# cameralight.net
KiCad netlist of a schematic drawn in EAGLE
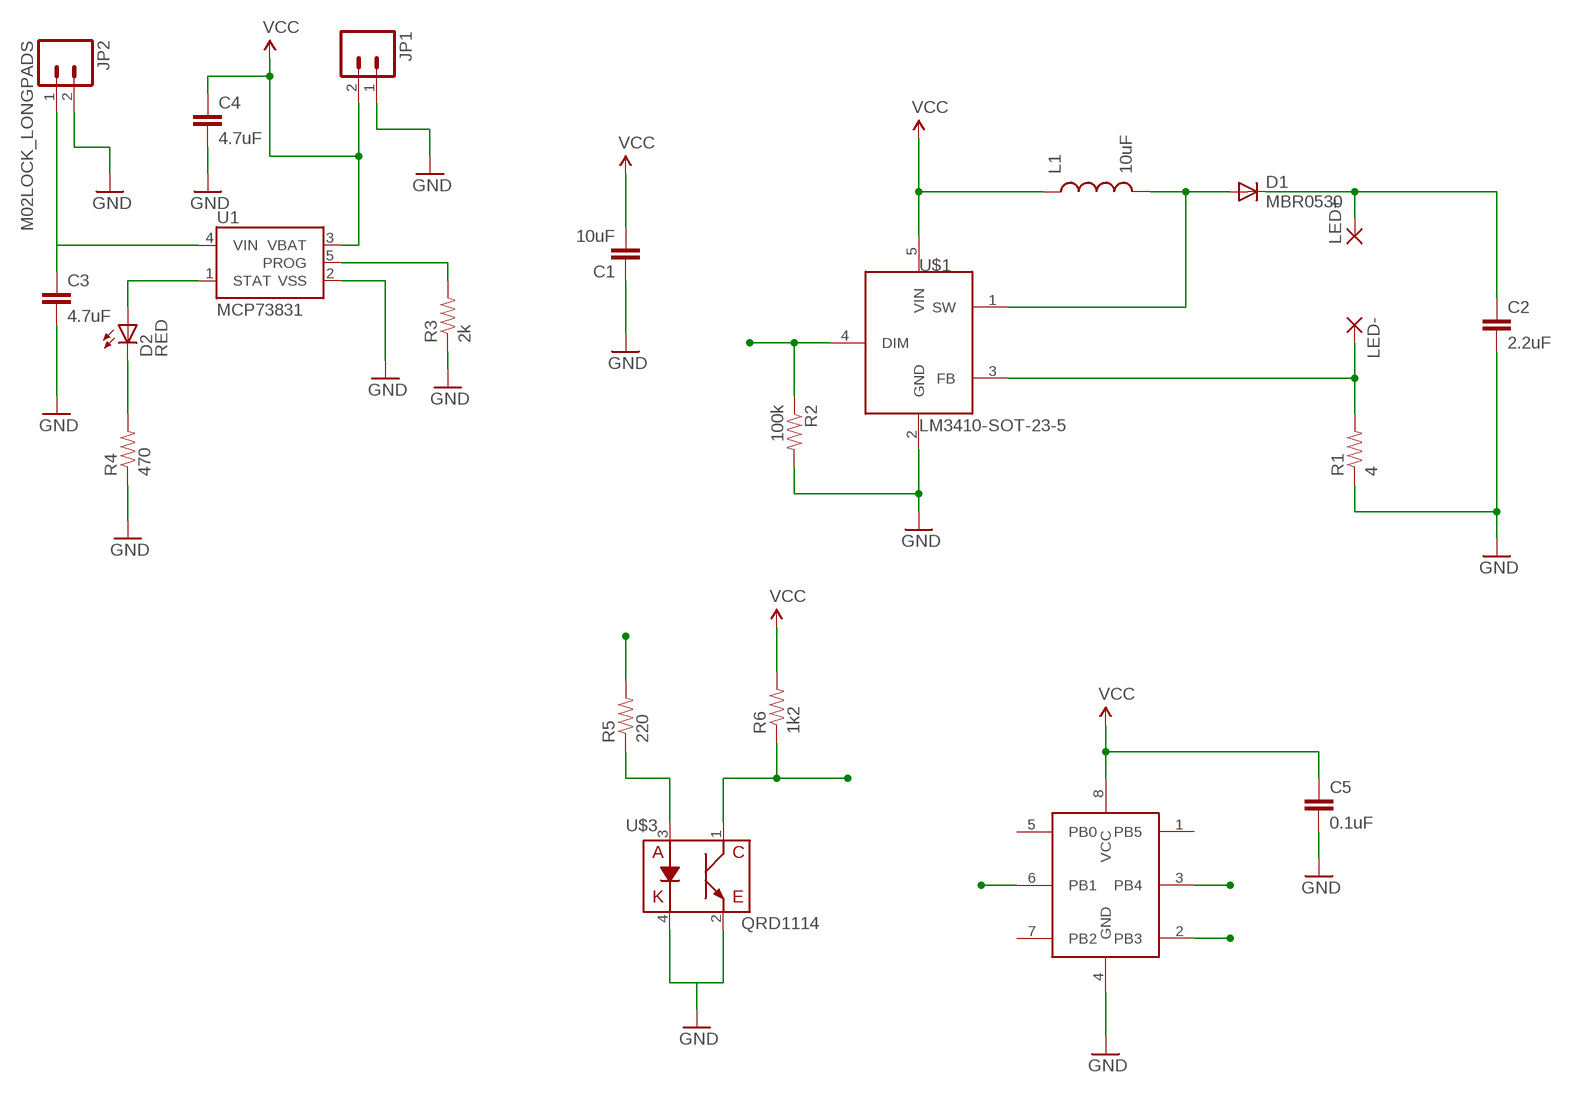
[diagram p0: schematic, sheet 1]

(export (version "E")
  (design (tool "Eeschema 10.0.6"))
  (components
    (comp (ref "C1")
      (value "10uF")
      (footprint "eagle-import:CTZ3")
      (libsource (lib "eagle-import") (part "SparkFun-Passives_CAPASMD"))
    )
    (comp (ref "C2")
      (value "2.2uF")
      (footprint "eagle-import:CTZ3")
      (libsource (lib "eagle-import") (part "SparkFun-Passives_CAPASMD"))
    )
    (comp (ref "C3")
      (value "4.7uF")
      (footprint "eagle-import:1206")
      (libsource (lib "eagle-import") (part "CAP1206"))
    )
    (comp (ref "C4")
      (value "4.7uF")
      (footprint "eagle-import:1206")
      (libsource (lib "eagle-import") (part "CAP1206"))
    )
    (comp (ref "C5")
      (value "0.1uF")
      (footprint "eagle-import:0603-CAP")
      (libsource (lib "eagle-import") (part "CAP0603-CAP"))
    )
    (comp (ref "D1")
      (value "MBR0530")
      (footprint "eagle-import:SOD123")
      (libsource (lib "eagle-import") (part "MBR0520LT"))
    )
    (comp (ref "D2")
      (value "RED")
      (footprint "eagle-import:LED-0603")
      (libsource (lib "eagle-import") (part "LED-RED0603"))
    )
    (comp (ref "JP1")
      (value "M02-JST-2MM-SMT")
      (footprint "eagle-import:JST-2-SMD")
      (libsource (lib "eagle-import") (part "M02-JST-2MM-SMT"))
    )
    (comp (ref "JP2")
      (value "M02LOCK_LONGPADS")
      (footprint "eagle-import:1X02_LOCK_LONGPADS")
      (libsource (lib "eagle-import") (part "M02LOCK_LONGPADS"))
    )
    (comp (ref "L1")
      (value "10uF")
      (footprint "eagle-import:CR54")
      (libsource (lib "eagle-import") (part "INDUCTORCR54"))
    )
    (comp (ref "LED+")
      (value "2,54/1,0")
      (footprint "eagle-import:2,54_1,0")
      (libsource (lib "eagle-import") (part "2,54/1,0"))
    )
    (comp (ref "LED-")
      (value "2,54/1,0")
      (footprint "eagle-import:2,54_1,0")
      (libsource (lib "eagle-import") (part "2,54/1,0"))
    )
    (comp (ref "R1")
      (value "4")
      (footprint "eagle-import:0603-RES")
      (libsource (lib "eagle-import") (part "RESISTOR0603-RES"))
    )
    (comp (ref "R2")
      (value "100k")
      (footprint "eagle-import:0603-RES")
      (libsource (lib "eagle-import") (part "RESISTOR0603-RES"))
    )
    (comp (ref "R3")
      (value "2k")
      (footprint "eagle-import:1206")
      (libsource (lib "eagle-import") (part "RESISTOR1206"))
    )
    (comp (ref "R4")
      (value "470")
      (footprint "eagle-import:0603-RES")
      (libsource (lib "eagle-import") (part "RESISTOR0603-RES"))
    )
    (comp (ref "R5")
      (value "220")
      (footprint "eagle-import:0603-RES")
      (libsource (lib "eagle-import") (part "RESISTOR0603-RES"))
    )
    (comp (ref "R6")
      (value "1k2")
      (footprint "eagle-import:0603-RES")
      (libsource (lib "eagle-import") (part "RESISTOR0603-RES"))
    )
    (comp (ref "U$1")
      (value "LM3410-SOT-23-5")
      (footprint "eagle-import:SOT-23-5")
      (libsource (lib "eagle-import") (part "LM3410-SOT-23-5"))
    )
    (comp (ref "U$2")
      (value "ATTINY13")
      (footprint "eagle-import:WSOIC-8")
      (libsource (lib "eagle-import") (part "ATTINY13"))
    )
    (comp (ref "U$3")
      (value "QRD1114")
      (footprint "eagle-import:QRD1114")
      (libsource (lib "eagle-import") (part "QRD1114"))
    )
    (comp (ref "U1")
      (value "MCP73831")
      (footprint "eagle-import:SOT23-5")
      (libsource (lib "eagle-import") (part "MCP73831"))
    )
  )
  (nets
    (net (code "1") (name "/DIM") (class "Default")
      (node (ref "R2") (pin "1") (pinfunction "1_1") (pintype "passive"))
      (node (ref "U$1") (pin "4") (pinfunction "DIM_4") (pintype "bidirectional"))
      (node (ref "U$2") (pin "6") (pinfunction "PB1_6") (pintype "bidirectional"))
    )
    (net (code "2") (name "/PROX_EN") (class "Default")
      (node (ref "R5") (pin "2") (pinfunction "2_2") (pintype "passive"))
      (node (ref "U$2") (pin "2") (pinfunction "PB3_2") (pintype "bidirectional"))
    )
    (net (code "3") (name "/PROX_SNS") (class "Default")
      (node (ref "R6") (pin "1") (pinfunction "1_1") (pintype "passive"))
      (node (ref "U$2") (pin "3") (pinfunction "PB4_3") (pintype "bidirectional"))
      (node (ref "U$3") (pin "1") (pinfunction "E_1") (pintype "bidirectional"))
    )
    (net (code "4") (name "GND") (class "Default")
      (node (ref "C1") (pin "+") (pinfunction "1_+") (pintype "passive"))
      (node (ref "C2") (pin "-") (pinfunction "2_-") (pintype "passive"))
      (node (ref "C3") (pin "2") (pinfunction "2_2") (pintype "passive"))
      (node (ref "C4") (pin "2") (pinfunction "2_2") (pintype "passive"))
      (node (ref "C5") (pin "2") (pinfunction "2_2") (pintype "passive"))
      (node (ref "JP1") (pin "1") (pinfunction "2_1") (pintype "passive"))
      (node (ref "JP2") (pin "2") (pinfunction "2_2") (pintype "passive"))
      (node (ref "R1") (pin "1") (pinfunction "1_1") (pintype "passive"))
      (node (ref "R2") (pin "2") (pinfunction "2_2") (pintype "passive"))
      (node (ref "R3") (pin "1") (pinfunction "1_1") (pintype "passive"))
      (node (ref "R4") (pin "1") (pinfunction "1_1") (pintype "passive"))
      (node (ref "U$1") (pin "2") (pinfunction "GND_2") (pintype "bidirectional"))
      (node (ref "U$2") (pin "4") (pinfunction "GND_4") (pintype "bidirectional"))
      (node (ref "U$3") (pin "2") (pinfunction "C_2") (pintype "bidirectional"))
      (node (ref "U$3") (pin "4") (pinfunction "K_4") (pintype "bidirectional"))
      (node (ref "U1") (pin "2") (pinfunction "VSS_2") (pintype "power_in"))
    )
    (net (code "5") (name "Net-(C2-1)") (class "Default")
      (node (ref "C2") (pin "+") (pinfunction "1_+") (pintype "passive"))
      (node (ref "D1") (pin "C") (pinfunction "C_C") (pintype "passive"))
      (node (ref "LED+") (pin "1") (pinfunction "P_1") (pintype "passive"))
    )
    (net (code "6") (name "Net-(D2-PadC)") (class "Default")
      (node (ref "D2") (pin "C") (pinfunction "C_C") (pintype "passive"))
      (node (ref "R4") (pin "2") (pinfunction "2_2") (pintype "passive"))
    )
    (net (code "7") (name "Net-(L1-2)") (class "Default")
      (node (ref "D1") (pin "A") (pinfunction "A_A") (pintype "passive"))
      (node (ref "L1") (pin "P$2") (pinfunction "2_P$2") (pintype "passive"))
      (node (ref "U$1") (pin "1") (pinfunction "SW_1") (pintype "bidirectional"))
    )
    (net (code "8") (name "Net-(LED--P)") (class "Default")
      (node (ref "LED-") (pin "1") (pinfunction "P_1") (pintype "passive"))
      (node (ref "R1") (pin "2") (pinfunction "2_2") (pintype "passive"))
      (node (ref "U$1") (pin "3") (pinfunction "FB_3") (pintype "bidirectional"))
    )
    (net (code "9") (name "Net-(U$3-A)") (class "Default")
      (node (ref "R5") (pin "1") (pinfunction "1_1") (pintype "passive"))
      (node (ref "U$3") (pin "3") (pinfunction "A_3") (pintype "bidirectional"))
    )
    (net (code "10") (name "Net-(U1-PROG)") (class "Default")
      (node (ref "R3") (pin "2") (pinfunction "2_2") (pintype "passive"))
      (node (ref "U1") (pin "5") (pinfunction "PROG_5") (pintype "input"))
    )
    (net (code "11") (name "Net-(U1-STAT)") (class "Default")
      (node (ref "D2") (pin "A") (pinfunction "A_A") (pintype "passive"))
      (node (ref "U1") (pin "1") (pinfunction "STAT_1") (pintype "output"))
    )
    (net (code "12") (name "Net-(U1-VIN)") (class "Default")
      (node (ref "C3") (pin "1") (pinfunction "1_1") (pintype "passive"))
      (node (ref "JP2") (pin "1") (pinfunction "1_1") (pintype "passive"))
      (node (ref "U1") (pin "4") (pinfunction "VIN_4") (pintype "power_in"))
    )
    (net (code "13") (name "VCC") (class "Default")
      (node (ref "C1") (pin "-") (pinfunction "2_-") (pintype "passive"))
      (node (ref "C4") (pin "1") (pinfunction "1_1") (pintype "passive"))
      (node (ref "C5") (pin "1") (pinfunction "1_1") (pintype "passive"))
      (node (ref "JP1") (pin "2") (pinfunction "1_2") (pintype "passive"))
      (node (ref "L1") (pin "P$1") (pinfunction "1_P$1") (pintype "passive"))
      (node (ref "R6") (pin "2") (pinfunction "2_2") (pintype "passive"))
      (node (ref "U$1") (pin "5") (pinfunction "VIN_5") (pintype "bidirectional"))
      (node (ref "U$2") (pin "8") (pinfunction "VCC_8") (pintype "bidirectional"))
      (node (ref "U1") (pin "3") (pinfunction "VBAT_3") (pintype "power_in"))
    )
    (net (code "14") (name "unconnected-(U$2-PB0-Pad5)") (class "Default")
      (node (ref "U$2") (pin "5") (pinfunction "PB0_5") (pintype "bidirectional"))
    )
    (net (code "15") (name "unconnected-(U$2-PB2-Pad7)") (class "Default")
      (node (ref "U$2") (pin "7") (pinfunction "PB2_7") (pintype "bidirectional"))
    )
    (net (code "16") (name "unconnected-(U$2-PB5-Pad1)") (class "Default")
      (node (ref "U$2") (pin "1") (pinfunction "PB5_1") (pintype "bidirectional"))
    )
  )
)
